# RaspberryPi-PICPgm-2.net
KiCad netlist of a schematic drawn in EAGLE
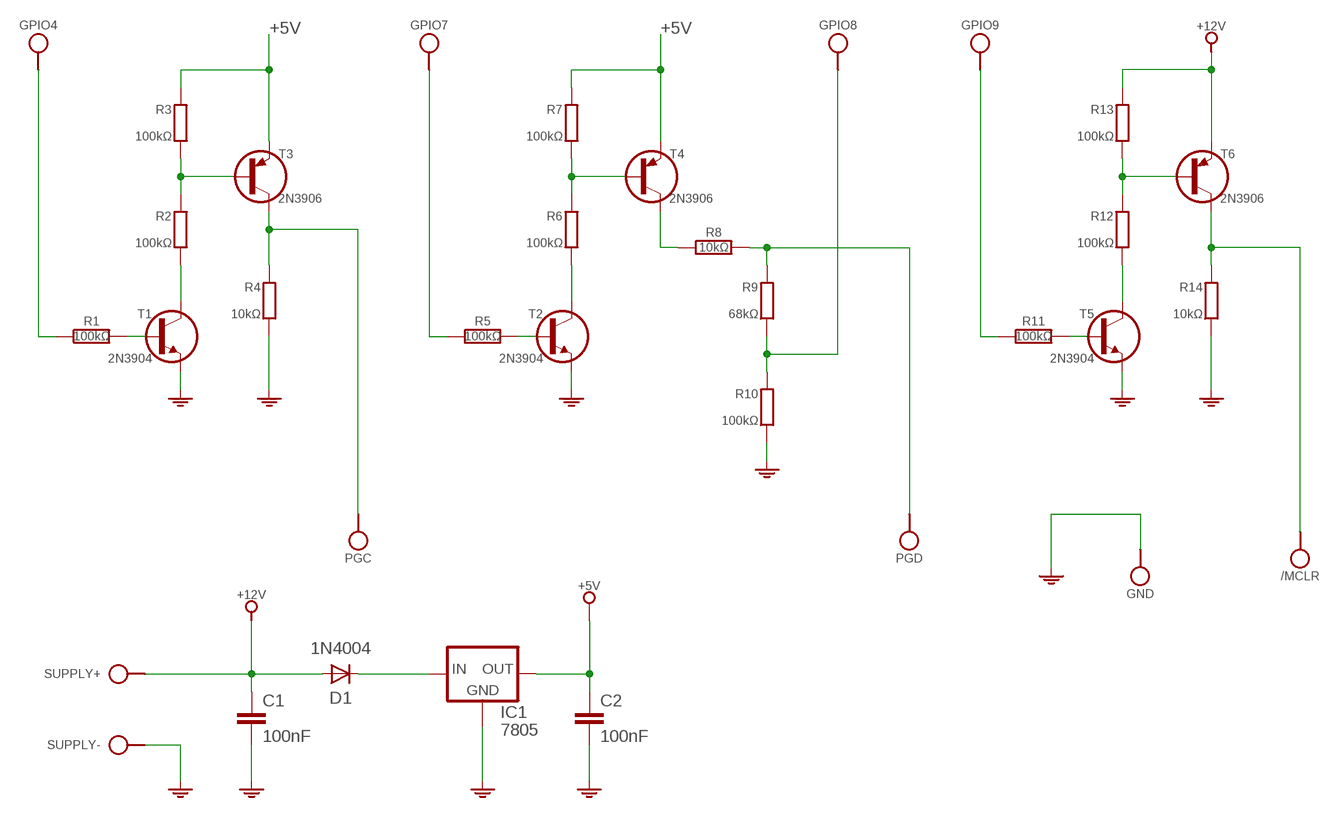
[diagram p0: schematic, sheet 1]

(export (version "E")
  (design (tool "Eeschema 10.0.6"))
  (components
    (comp (ref "/MCLR")
      (value "VPORT")
      (footprint "eagle-import:SPAD")
      (libsource (lib "eagle-import") (part "VPORT"))
    )
    (comp (ref "C1")
      (value "100nF")
      (footprint "eagle-import:C050-025X075")
      (libsource (lib "eagle-import") (part "C050-025X075"))
    )
    (comp (ref "C2")
      (value "100nF")
      (footprint "eagle-import:C050-025X075")
      (libsource (lib "eagle-import") (part "C050-025X075"))
    )
    (comp (ref "D1")
      (value "1N4004")
      (footprint "eagle-import:DO41-10")
      (libsource (lib "eagle-import") (part "1N4004-H"))
    )
    (comp (ref "GND")
      (value "VPORT")
      (footprint "eagle-import:SPAD")
      (libsource (lib "eagle-import") (part "VPORT"))
    )
    (comp (ref "GPIO4")
      (value "VPORT")
      (footprint "eagle-import:SPAD")
      (libsource (lib "eagle-import") (part "VPORT"))
    )
    (comp (ref "GPIO7")
      (value "VPORT")
      (footprint "eagle-import:SPAD")
      (libsource (lib "eagle-import") (part "VPORT"))
    )
    (comp (ref "GPIO8")
      (value "VPORT")
      (footprint "eagle-import:SPAD")
      (libsource (lib "eagle-import") (part "VPORT"))
    )
    (comp (ref "GPIO9")
      (value "VPORT")
      (footprint "eagle-import:SPAD")
      (libsource (lib "eagle-import") (part "VPORT"))
    )
    (comp (ref "IC1")
      (value "7805")
      (footprint "eagle-import:TO220")
      (libsource (lib "eagle-import") (part "LM78"))
    )
    (comp (ref "PGC")
      (value "VPORT")
      (footprint "eagle-import:SPAD")
      (libsource (lib "eagle-import") (part "VPORT"))
    )
    (comp (ref "PGD")
      (value "VPORT")
      (footprint "eagle-import:SPAD")
      (libsource (lib "eagle-import") (part "VPORT"))
    )
    (comp (ref "R1")
      (value "100kΩ")
      (footprint "eagle-import:0204_10")
      (libsource (lib "eagle-import") (part "R-H0204/10"))
    )
    (comp (ref "R2")
      (value "100kΩ")
      (footprint "eagle-import:0204_10-V")
      (libsource (lib "eagle-import") (part "R0204/10-V"))
    )
    (comp (ref "R3")
      (value "100kΩ")
      (footprint "eagle-import:0204_10-V")
      (libsource (lib "eagle-import") (part "R0204/10-V"))
    )
    (comp (ref "R4")
      (value "10kΩ")
      (footprint "eagle-import:0204_10-V")
      (libsource (lib "eagle-import") (part "R0204/10-V"))
    )
    (comp (ref "R5")
      (value "100kΩ")
      (footprint "eagle-import:0204_10")
      (libsource (lib "eagle-import") (part "R-H0204/10"))
    )
    (comp (ref "R6")
      (value "100kΩ")
      (footprint "eagle-import:0204_10-V")
      (libsource (lib "eagle-import") (part "R0204/10-V"))
    )
    (comp (ref "R7")
      (value "100kΩ")
      (footprint "eagle-import:0204_10-V")
      (libsource (lib "eagle-import") (part "R0204/10-V"))
    )
    (comp (ref "R8")
      (value "10kΩ")
      (footprint "eagle-import:0204_10")
      (libsource (lib "eagle-import") (part "R-H0204/10"))
    )
    (comp (ref "R9")
      (value "68kΩ")
      (footprint "eagle-import:0204_10-V")
      (libsource (lib "eagle-import") (part "R0204/10-V"))
    )
    (comp (ref "R10")
      (value "100kΩ")
      (footprint "eagle-import:0204_10-V")
      (libsource (lib "eagle-import") (part "R0204/10-V"))
    )
    (comp (ref "R11")
      (value "100kΩ")
      (footprint "eagle-import:0204_10")
      (libsource (lib "eagle-import") (part "R-H0204/10"))
    )
    (comp (ref "R12")
      (value "100kΩ")
      (footprint "eagle-import:0204_10-V")
      (libsource (lib "eagle-import") (part "R0204/10-V"))
    )
    (comp (ref "R13")
      (value "100kΩ")
      (footprint "eagle-import:0204_10-V")
      (libsource (lib "eagle-import") (part "R0204/10-V"))
    )
    (comp (ref "R14")
      (value "10kΩ")
      (footprint "eagle-import:0204_10-V")
      (libsource (lib "eagle-import") (part "R0204/10-V"))
    )
    (comp (ref "SUPPLY")
      (value "SPAD+--+")
      (footprint "eagle-import:SPAD-+")
      (libsource (lib "eagle-import") (part "SPAD+--+"))
    )
    (comp (ref "T1")
      (value "2N3904")
      (footprint "eagle-import:TO92-EBC")
      (libsource (lib "eagle-import") (part "2N3904EBC"))
    )
    (comp (ref "T2")
      (value "2N3904")
      (footprint "eagle-import:TO92-EBC")
      (libsource (lib "eagle-import") (part "2N3904EBC"))
    )
    (comp (ref "T3")
      (value "2N3906")
      (footprint "eagle-import:TO92-EBC")
      (libsource (lib "eagle-import") (part "2N3906TO92-EBC"))
    )
    (comp (ref "T4")
      (value "2N3906")
      (footprint "eagle-import:TO92-EBC")
      (libsource (lib "eagle-import") (part "2N3906TO92-EBC"))
    )
    (comp (ref "T5")
      (value "2N3904")
      (footprint "eagle-import:TO92-EBC")
      (libsource (lib "eagle-import") (part "2N3904EBC"))
    )
    (comp (ref "T6")
      (value "2N3906")
      (footprint "eagle-import:TO92-EBC")
      (libsource (lib "eagle-import") (part "2N3906TO92-EBC"))
    )
  )
  (nets
    (net (code "1") (name "+5V") (class "Default")
      (node (ref "C2") (pin "1") (pinfunction "1_1") (pintype "passive"))
      (node (ref "IC1") (pin "3") (pinfunction "OUT_3") (pintype "output"))
      (node (ref "R3") (pin "1") (pinfunction "2_1") (pintype "passive"))
      (node (ref "R7") (pin "1") (pinfunction "2_1") (pintype "passive"))
      (node (ref "T3") (pin "E") (pinfunction "E_E") (pintype "passive"))
      (node (ref "T4") (pin "E") (pinfunction "E_E") (pintype "passive"))
    )
    (net (code "2") (name "+12V") (class "Default")
      (node (ref "C1") (pin "1") (pinfunction "1_1") (pintype "passive"))
      (node (ref "D1") (pin "A") (pinfunction "A_A") (pintype "passive"))
      (node (ref "R13") (pin "1") (pinfunction "2_1") (pintype "passive"))
      (node (ref "SUPPLY") (pin "2") (pinfunction "P$1_2") (pintype "passive"))
      (node (ref "T6") (pin "E") (pinfunction "E_E") (pintype "passive"))
    )
    (net (code "3") (name "GND") (class "Default")
      (node (ref "C1") (pin "2") (pinfunction "2_2") (pintype "passive"))
      (node (ref "C2") (pin "2") (pinfunction "2_2") (pintype "passive"))
      (node (ref "GND") (pin "1") (pinfunction "P$1_1") (pintype "passive"))
      (node (ref "IC1") (pin "2") (pinfunction "GND_2") (pintype "input"))
      (node (ref "R10") (pin "2") (pinfunction "1_2") (pintype "passive"))
      (node (ref "R14") (pin "2") (pinfunction "1_2") (pintype "passive"))
      (node (ref "R4") (pin "2") (pinfunction "1_2") (pintype "passive"))
      (node (ref "SUPPLY") (pin "1") (pinfunction "P$1_1") (pintype "passive"))
      (node (ref "T1") (pin "E") (pinfunction "E_E") (pintype "passive"))
      (node (ref "T2") (pin "E") (pinfunction "E_E") (pintype "passive"))
      (node (ref "T5") (pin "E") (pinfunction "E_E") (pintype "passive"))
    )
    (net (code "4") (name "Net-(/MCLR-P$1)") (class "Default")
      (node (ref "/MCLR") (pin "1") (pinfunction "P$1_1") (pintype "passive"))
      (node (ref "R14") (pin "1") (pinfunction "2_1") (pintype "passive"))
      (node (ref "T6") (pin "C") (pinfunction "C_C") (pintype "passive"))
    )
    (net (code "5") (name "Net-(GPIO4-P$1)") (class "Default")
      (node (ref "GPIO4") (pin "1") (pinfunction "P$1_1") (pintype "passive"))
      (node (ref "R1") (pin "1") (pinfunction "1_1") (pintype "passive"))
    )
    (net (code "6") (name "Net-(GPIO7-P$1)") (class "Default")
      (node (ref "GPIO7") (pin "1") (pinfunction "P$1_1") (pintype "passive"))
      (node (ref "R5") (pin "1") (pinfunction "1_1") (pintype "passive"))
    )
    (net (code "7") (name "Net-(GPIO8-P$1)") (class "Default")
      (node (ref "GPIO8") (pin "1") (pinfunction "P$1_1") (pintype "passive"))
      (node (ref "R10") (pin "1") (pinfunction "2_1") (pintype "passive"))
      (node (ref "R9") (pin "2") (pinfunction "1_2") (pintype "passive"))
    )
    (net (code "8") (name "Net-(GPIO9-P$1)") (class "Default")
      (node (ref "GPIO9") (pin "1") (pinfunction "P$1_1") (pintype "passive"))
      (node (ref "R11") (pin "1") (pinfunction "1_1") (pintype "passive"))
    )
    (net (code "9") (name "Net-(IC1-IN)") (class "Default")
      (node (ref "D1") (pin "C") (pinfunction "C_C") (pintype "passive"))
      (node (ref "IC1") (pin "1") (pinfunction "IN_1") (pintype "input"))
    )
    (net (code "10") (name "Net-(PGC-P$1)") (class "Default")
      (node (ref "PGC") (pin "1") (pinfunction "P$1_1") (pintype "passive"))
      (node (ref "R4") (pin "1") (pinfunction "2_1") (pintype "passive"))
      (node (ref "T3") (pin "C") (pinfunction "C_C") (pintype "passive"))
    )
    (net (code "11") (name "Net-(PGD-P$1)") (class "Default")
      (node (ref "PGD") (pin "1") (pinfunction "P$1_1") (pintype "passive"))
      (node (ref "R8") (pin "2") (pinfunction "2_2") (pintype "passive"))
      (node (ref "R9") (pin "1") (pinfunction "2_1") (pintype "passive"))
    )
    (net (code "12") (name "Net-(R1-Pad2)") (class "Default")
      (node (ref "R1") (pin "2") (pinfunction "2_2") (pintype "passive"))
      (node (ref "T1") (pin "B") (pinfunction "B_B") (pintype "passive"))
    )
    (net (code "13") (name "Net-(R2-1)") (class "Default")
      (node (ref "R2") (pin "2") (pinfunction "1_2") (pintype "passive"))
      (node (ref "T1") (pin "C") (pinfunction "C_C") (pintype "passive"))
    )
    (net (code "14") (name "Net-(R2-2)") (class "Default")
      (node (ref "R2") (pin "1") (pinfunction "2_1") (pintype "passive"))
      (node (ref "R3") (pin "2") (pinfunction "1_2") (pintype "passive"))
      (node (ref "T3") (pin "B") (pinfunction "B_B") (pintype "passive"))
    )
    (net (code "15") (name "Net-(R5-Pad2)") (class "Default")
      (node (ref "R5") (pin "2") (pinfunction "2_2") (pintype "passive"))
      (node (ref "T2") (pin "B") (pinfunction "B_B") (pintype "passive"))
    )
    (net (code "16") (name "Net-(R6-1)") (class "Default")
      (node (ref "R6") (pin "2") (pinfunction "1_2") (pintype "passive"))
      (node (ref "T2") (pin "C") (pinfunction "C_C") (pintype "passive"))
    )
    (net (code "17") (name "Net-(R6-2)") (class "Default")
      (node (ref "R6") (pin "1") (pinfunction "2_1") (pintype "passive"))
      (node (ref "R7") (pin "2") (pinfunction "1_2") (pintype "passive"))
      (node (ref "T4") (pin "B") (pinfunction "B_B") (pintype "passive"))
    )
    (net (code "18") (name "Net-(R8-Pad1)") (class "Default")
      (node (ref "R8") (pin "1") (pinfunction "1_1") (pintype "passive"))
      (node (ref "T4") (pin "C") (pinfunction "C_C") (pintype "passive"))
    )
    (net (code "19") (name "Net-(R11-Pad2)") (class "Default")
      (node (ref "R11") (pin "2") (pinfunction "2_2") (pintype "passive"))
      (node (ref "T5") (pin "B") (pinfunction "B_B") (pintype "passive"))
    )
    (net (code "20") (name "Net-(R12-1)") (class "Default")
      (node (ref "R12") (pin "2") (pinfunction "1_2") (pintype "passive"))
      (node (ref "T5") (pin "C") (pinfunction "C_C") (pintype "passive"))
    )
    (net (code "21") (name "Net-(R12-2)") (class "Default")
      (node (ref "R12") (pin "1") (pinfunction "2_1") (pintype "passive"))
      (node (ref "R13") (pin "2") (pinfunction "1_2") (pintype "passive"))
      (node (ref "T6") (pin "B") (pinfunction "B_B") (pintype "passive"))
    )
  )
)
